# motherboard-board_cleanup.net
KiCad netlist of a schematic drawn in EAGLE
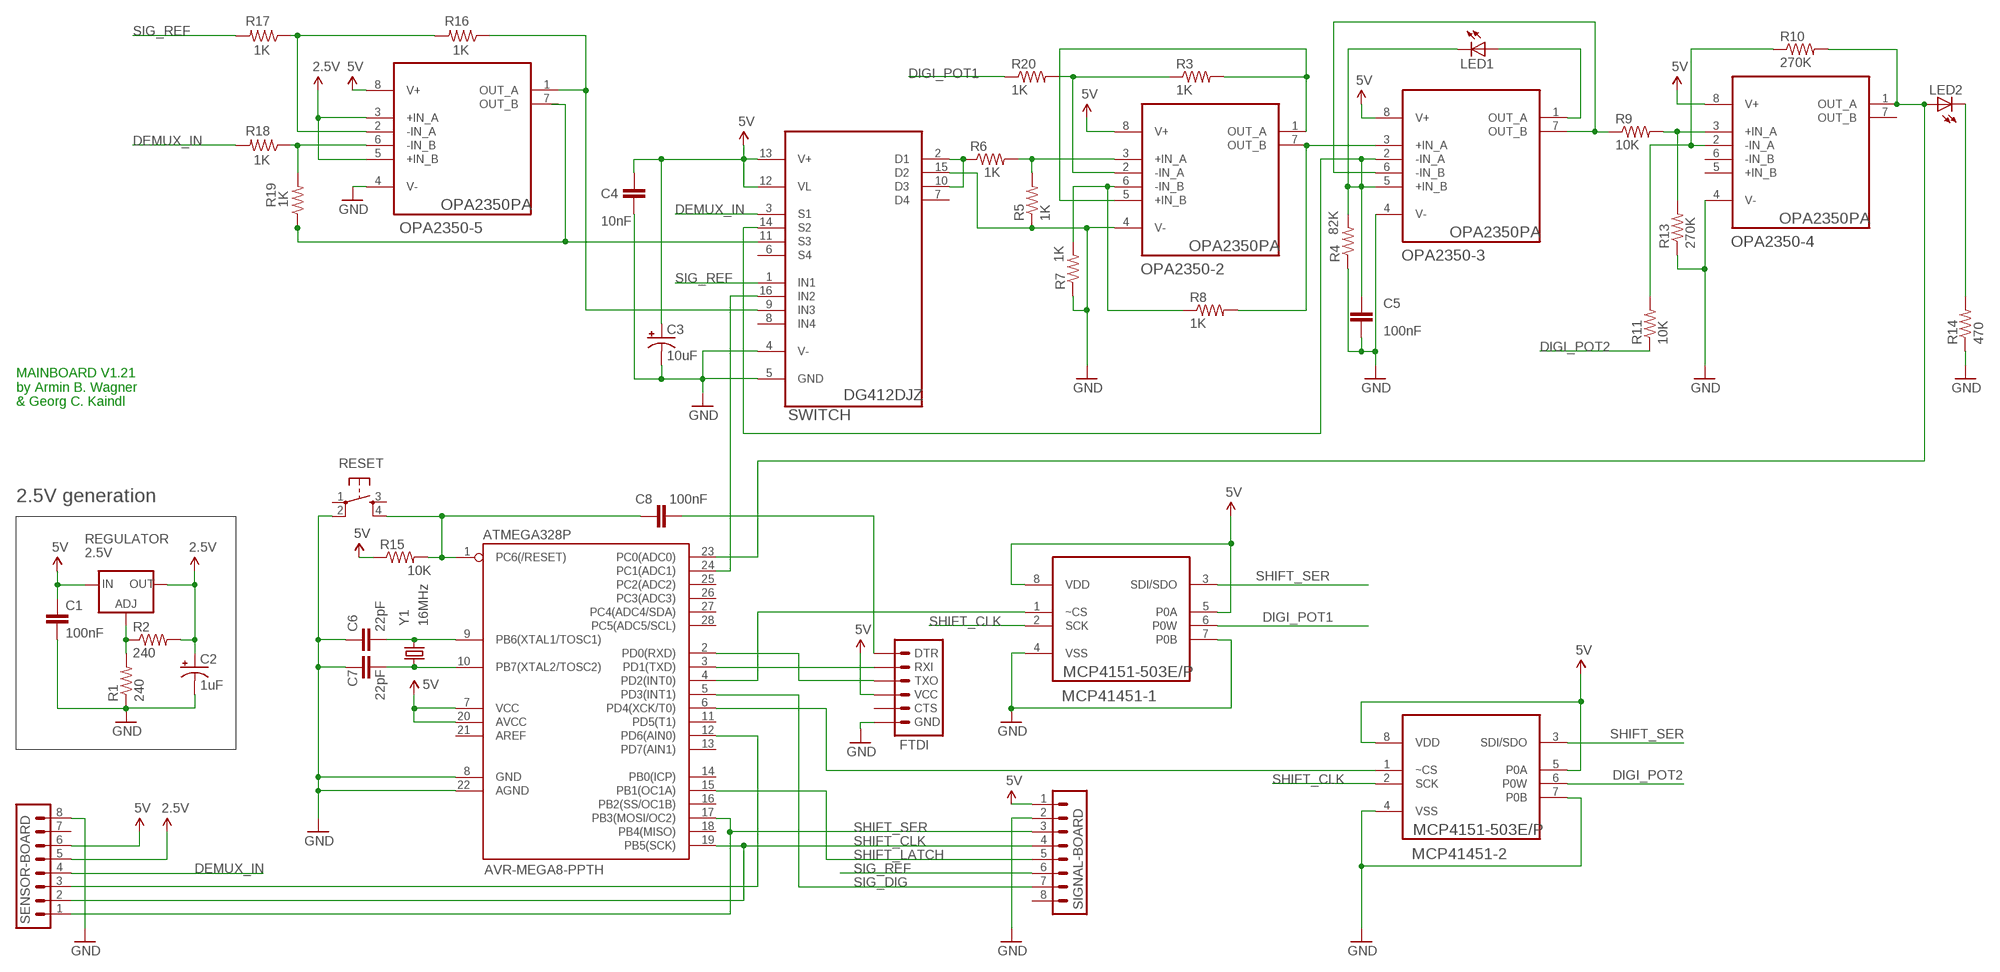
[diagram p0: schematic, sheet 1]

(export (version "E")
  (design (tool "Eeschema 10.0.6"))
  (components
    (comp (ref "ATMEGA328P")
      (value "AVR-MEGA8-PPTH")
      (footprint "eagle-import:DIL28-3")
      (libsource (lib "eagle-import") (part "AVR-MEGA8-PPTH"))
    )
    (comp (ref "C1")
      (value "100nF")
      (footprint "eagle-import:CAP-PTH-SMALL")
      (libsource (lib "eagle-import") (part "CAPPTH"))
    )
    (comp (ref "C2")
      (value "1uF")
      (footprint "eagle-import:CPOL-RADIAL-10UF-25V")
      (libsource (lib "eagle-import") (part "CAP_POLPTH2"))
    )
    (comp (ref "C3")
      (value "10uF")
      (footprint "eagle-import:CPOL-RADIAL-10UF-25V")
      (libsource (lib "eagle-import") (part "CAP_POLPTH2"))
    )
    (comp (ref "C4")
      (value "10nF")
      (footprint "eagle-import:CAP-PTH-SMALL")
      (libsource (lib "eagle-import") (part "CAPPTH"))
    )
    (comp (ref "C5")
      (value "100nF")
      (footprint "eagle-import:CAP-PTH-SMALL")
      (libsource (lib "eagle-import") (part "CAPPTH"))
    )
    (comp (ref "C6")
      (value "22pF")
      (footprint "eagle-import:CAP-PTH-SMALL2")
      (libsource (lib "eagle-import") (part "CAPPTH2"))
    )
    (comp (ref "C7")
      (value "22pF")
      (footprint "eagle-import:CAP-PTH-SMALL2")
      (libsource (lib "eagle-import") (part "CAPPTH2"))
    )
    (comp (ref "C8")
      (value "100nF")
      (footprint "eagle-import:CAP-PTH-SMALL2")
      (libsource (lib "eagle-import") (part "CAPPTH2"))
    )
    (comp (ref "FTDI")
      (value "ARDUINO_SERIAL_PROGRAMLONGPADS")
      (footprint "eagle-import:1X06_LONGPADS")
      (libsource (lib "eagle-import") (part "ARDUINO_SERIAL_PROGRAMLONGPADS"))
    )
    (comp (ref "LED1")
      (value "LED3MM")
      (footprint "eagle-import:LED3MM")
      (libsource (lib "eagle-import") (part "LED3MM"))
    )
    (comp (ref "LED2")
      (value "LED5MM")
      (footprint "eagle-import:LED5MM")
      (libsource (lib "eagle-import") (part "LED5MM"))
    )
    (comp (ref "MCP41451-1")
      (value "MCP4151-503E/P")
      (footprint "eagle-import:DIP254P762X533-8")
      (libsource (lib "eagle-import") (part "MCP4151-503E/P"))
    )
    (comp (ref "MCP41451-2")
      (value "MCP4151-503E/P")
      (footprint "eagle-import:DIP254P762X533-8")
      (libsource (lib "eagle-import") (part "MCP4151-503E/P"))
    )
    (comp (ref "OPA2350-2")
      (value "OPA2350PA")
      (footprint "eagle-import:DIP254P762X508-8")
      (libsource (lib "eagle-import") (part "OPA2350PA"))
    )
    (comp (ref "OPA2350-3")
      (value "OPA2350PA")
      (footprint "eagle-import:DIP254P762X508-8")
      (libsource (lib "eagle-import") (part "OPA2350PA"))
    )
    (comp (ref "OPA2350-4")
      (value "OPA2350PA")
      (footprint "eagle-import:DIP254P762X508-8")
      (libsource (lib "eagle-import") (part "OPA2350PA"))
    )
    (comp (ref "OPA2350-5")
      (value "OPA2350PA")
      (footprint "eagle-import:DIP254P762X508-8")
      (libsource (lib "eagle-import") (part "OPA2350PA"))
    )
    (comp (ref "R1")
      (value "240")
      (footprint "eagle-import:AXIAL-0.3")
      (libsource (lib "eagle-import") (part "RESISTORAXIAL-0.3"))
    )
    (comp (ref "R2")
      (value "240")
      (footprint "eagle-import:AXIAL-0.3")
      (libsource (lib "eagle-import") (part "RESISTORAXIAL-0.3"))
    )
    (comp (ref "R3")
      (value "1K")
      (footprint "eagle-import:AXIAL-0.3")
      (libsource (lib "eagle-import") (part "RESISTORAXIAL-0.3"))
    )
    (comp (ref "R4")
      (value "82K")
      (footprint "eagle-import:AXIAL-0.3")
      (libsource (lib "eagle-import") (part "RESISTORAXIAL-0.3"))
    )
    (comp (ref "R5")
      (value "1K")
      (footprint "eagle-import:AXIAL-0.3")
      (libsource (lib "eagle-import") (part "RESISTORAXIAL-0.3"))
    )
    (comp (ref "R6")
      (value "1K")
      (footprint "eagle-import:AXIAL-0.3")
      (libsource (lib "eagle-import") (part "RESISTORAXIAL-0.3"))
    )
    (comp (ref "R7")
      (value "1K")
      (footprint "eagle-import:AXIAL-0.3")
      (libsource (lib "eagle-import") (part "RESISTORAXIAL-0.3"))
    )
    (comp (ref "R8")
      (value "1K")
      (footprint "eagle-import:AXIAL-0.3")
      (libsource (lib "eagle-import") (part "RESISTORAXIAL-0.3"))
    )
    (comp (ref "R9")
      (value "10K")
      (footprint "eagle-import:AXIAL-0.3")
      (libsource (lib "eagle-import") (part "RESISTORAXIAL-0.3"))
    )
    (comp (ref "R10")
      (value "270K")
      (footprint "eagle-import:AXIAL-0.3")
      (libsource (lib "eagle-import") (part "RESISTORAXIAL-0.3"))
    )
    (comp (ref "R11")
      (value "10K")
      (footprint "eagle-import:AXIAL-0.3")
      (libsource (lib "eagle-import") (part "RESISTORAXIAL-0.3"))
    )
    (comp (ref "R13")
      (value "270K")
      (footprint "eagle-import:AXIAL-0.3")
      (libsource (lib "eagle-import") (part "RESISTORAXIAL-0.3"))
    )
    (comp (ref "R14")
      (value "470")
      (footprint "eagle-import:AXIAL-0.3")
      (libsource (lib "eagle-import") (part "RESISTORAXIAL-0.3"))
    )
    (comp (ref "R15")
      (value "10K")
      (footprint "eagle-import:AXIAL-0.3")
      (libsource (lib "eagle-import") (part "RESISTORAXIAL-0.3"))
    )
    (comp (ref "R16")
      (value "1K")
      (footprint "eagle-import:AXIAL-0.3")
      (libsource (lib "eagle-import") (part "RESISTORAXIAL-0.3"))
    )
    (comp (ref "R17")
      (value "1K")
      (footprint "eagle-import:AXIAL-0.3")
      (libsource (lib "eagle-import") (part "RESISTORAXIAL-0.3"))
    )
    (comp (ref "R18")
      (value "1K")
      (footprint "eagle-import:AXIAL-0.3")
      (libsource (lib "eagle-import") (part "RESISTORAXIAL-0.3"))
    )
    (comp (ref "R19")
      (value "1K")
      (footprint "eagle-import:AXIAL-0.3")
      (libsource (lib "eagle-import") (part "RESISTORAXIAL-0.3"))
    )
    (comp (ref "R20")
      (value "1K")
      (footprint "eagle-import:AXIAL-0.3")
      (libsource (lib "eagle-import") (part "RESISTORAXIAL-0.3"))
    )
    (comp (ref "REGULATOR")
      (value "2.5V")
      (footprint "eagle-import:TO220-ADJ")
      (libsource (lib "eagle-import") (part "V_REG_317SINK"))
    )
    (comp (ref "RESET")
      (value "TAC_SWITCHPTH")
      (footprint "eagle-import:TACTILE-PTH")
      (libsource (lib "eagle-import") (part "TAC_SWITCHPTH"))
    )
    (comp (ref "SENSOR-BOARD")
      (value "M08LONGPADS")
      (footprint "eagle-import:1X08_LONGPADS")
      (libsource (lib "eagle-import") (part "M08LONGPADS"))
    )
    (comp (ref "SIGNAL-BOARD")
      (value "M08LONGPADS")
      (footprint "eagle-import:1X08_LONGPADS")
      (libsource (lib "eagle-import") (part "M08LONGPADS"))
    )
    (comp (ref "SWITCH")
      (value "DG412DJZ")
      (footprint "eagle-import:DIP254P762X533-16")
      (libsource (lib "eagle-import") (part "DG412DJZ"))
    )
    (comp (ref "Y1")
      (value "16MHz")
      (footprint "eagle-import:HC49US")
      (libsource (lib "eagle-import") (part "CRYSTALHC49US"))
    )
  )
  (nets
    (net (code "1") (name "/DEMUX_IN") (class "Default")
      (node (ref "R18") (pin "P$2") (pinfunction "2_P$2") (pintype "passive"))
      (node (ref "SENSOR-BOARD") (pin "4") (pinfunction "4_4") (pintype "passive"))
      (node (ref "SWITCH") (pin "3") (pinfunction "S1_3") (pintype "input"))
    )
    (net (code "2") (name "/DIGI_POT1") (class "Default")
      (node (ref "MCP41451-1") (pin "6") (pinfunction "P0W_6") (pintype "passive"))
      (node (ref "R20") (pin "P$1") (pinfunction "1_P$1") (pintype "passive"))
    )
    (net (code "3") (name "/DIGI_POT2") (class "Default")
      (node (ref "MCP41451-2") (pin "6") (pinfunction "P0W_6") (pintype "passive"))
      (node (ref "R11") (pin "P$1") (pinfunction "1_P$1") (pintype "passive"))
    )
    (net (code "4") (name "/SHIFT_CLK") (class "Default")
      (node (ref "ATMEGA328P") (pin "19") (pinfunction "PB5(SCK)_19") (pintype "bidirectional"))
      (node (ref "MCP41451-1") (pin "2") (pinfunction "SCK_2") (pintype "input"))
      (node (ref "MCP41451-2") (pin "2") (pinfunction "SCK_2") (pintype "input"))
      (node (ref "SENSOR-BOARD") (pin "2") (pinfunction "2_2") (pintype "passive"))
      (node (ref "SIGNAL-BOARD") (pin "4") (pinfunction "4_4") (pintype "passive"))
    )
    (net (code "5") (name "/SHIFT_LATCH") (class "Default")
      (node (ref "ATMEGA328P") (pin "15") (pinfunction "PB1(OC1A)_15") (pintype "bidirectional"))
      (node (ref "SIGNAL-BOARD") (pin "5") (pinfunction "5_5") (pintype "passive"))
    )
    (net (code "6") (name "/SHIFT_SER") (class "Default")
      (node (ref "ATMEGA328P") (pin "17") (pinfunction "PB3(MOSI/OC2)_17") (pintype "bidirectional"))
      (node (ref "MCP41451-1") (pin "3") (pinfunction "SDI/SDO_3") (pintype "bidirectional"))
      (node (ref "MCP41451-2") (pin "3") (pinfunction "SDI/SDO_3") (pintype "bidirectional"))
      (node (ref "SENSOR-BOARD") (pin "1") (pinfunction "1_1") (pintype "passive"))
      (node (ref "SIGNAL-BOARD") (pin "3") (pinfunction "3_3") (pintype "passive"))
    )
    (net (code "7") (name "/SIG_DIG") (class "Default")
      (node (ref "ATMEGA328P") (pin "5") (pinfunction "PD3(INT1)_5") (pintype "bidirectional"))
      (node (ref "SIGNAL-BOARD") (pin "7") (pinfunction "7_7") (pintype "passive"))
    )
    (net (code "8") (name "/SIG_REF") (class "Default")
      (node (ref "R17") (pin "P$2") (pinfunction "2_P$2") (pintype "passive"))
      (node (ref "SIGNAL-BOARD") (pin "6") (pinfunction "6_6") (pintype "passive"))
      (node (ref "SWITCH") (pin "1") (pinfunction "IN1_1") (pintype "input"))
    )
    (net (code "9") (name "2.5V") (class "Default")
      (node (ref "C2") (pin "1") (pinfunction "+_1") (pintype "passive"))
      (node (ref "OPA2350-5") (pin "3") (pinfunction "+IN_A_3") (pintype "input"))
      (node (ref "OPA2350-5") (pin "5") (pinfunction "+IN_B_5") (pintype "input"))
      (node (ref "R2") (pin "P$2") (pinfunction "2_P$2") (pintype "passive"))
      (node (ref "REGULATOR") (pin "OUT") (pinfunction "OUT_OUT") (pintype "output"))
      (node (ref "SENSOR-BOARD") (pin "5") (pinfunction "5_5") (pintype "passive"))
    )
    (net (code "10") (name "5V") (class "Default")
      (node (ref "ATMEGA328P") (pin "20") (pinfunction "AVCC_20") (pintype "bidirectional"))
      (node (ref "ATMEGA328P") (pin "7") (pinfunction "VCC_7") (pintype "bidirectional"))
      (node (ref "C1") (pin "1") (pinfunction "1_1") (pintype "passive"))
      (node (ref "C3") (pin "1") (pinfunction "+_1") (pintype "passive"))
      (node (ref "C4") (pin "1") (pinfunction "1_1") (pintype "passive"))
      (node (ref "FTDI") (pin "4") (pinfunction "VCC_4") (pintype "passive"))
      (node (ref "MCP41451-1") (pin "5") (pinfunction "P0A_5") (pintype "passive"))
      (node (ref "MCP41451-1") (pin "8") (pinfunction "VDD_8") (pintype "power_in"))
      (node (ref "MCP41451-2") (pin "5") (pinfunction "P0A_5") (pintype "passive"))
      (node (ref "MCP41451-2") (pin "8") (pinfunction "VDD_8") (pintype "power_in"))
      (node (ref "OPA2350-2") (pin "8") (pinfunction "V+_8") (pintype "power_in"))
      (node (ref "OPA2350-3") (pin "8") (pinfunction "V+_8") (pintype "power_in"))
      (node (ref "OPA2350-4") (pin "8") (pinfunction "V+_8") (pintype "power_in"))
      (node (ref "OPA2350-5") (pin "8") (pinfunction "V+_8") (pintype "power_in"))
      (node (ref "R15") (pin "P$1") (pinfunction "1_P$1") (pintype "passive"))
      (node (ref "REGULATOR") (pin "IN") (pinfunction "IN_IN") (pintype "input"))
      (node (ref "SENSOR-BOARD") (pin "6") (pinfunction "6_6") (pintype "passive"))
      (node (ref "SIGNAL-BOARD") (pin "1") (pinfunction "1_1") (pintype "passive"))
      (node (ref "SWITCH") (pin "12") (pinfunction "VL_12") (pintype "power_in"))
      (node (ref "SWITCH") (pin "13") (pinfunction "V+_13") (pintype "power_in"))
    )
    (net (code "11") (name "GND") (class "Default")
      (node (ref "ATMEGA328P") (pin "22") (pinfunction "AGND_22") (pintype "bidirectional"))
      (node (ref "ATMEGA328P") (pin "8") (pinfunction "GND_8") (pintype "bidirectional"))
      (node (ref "C1") (pin "2") (pinfunction "2_2") (pintype "passive"))
      (node (ref "C2") (pin "2") (pinfunction "-_2") (pintype "passive"))
      (node (ref "C3") (pin "2") (pinfunction "-_2") (pintype "passive"))
      (node (ref "C4") (pin "2") (pinfunction "2_2") (pintype "passive"))
      (node (ref "C5") (pin "2") (pinfunction "2_2") (pintype "passive"))
      (node (ref "C6") (pin "1") (pinfunction "1_1") (pintype "passive"))
      (node (ref "C7") (pin "1") (pinfunction "1_1") (pintype "passive"))
      (node (ref "FTDI") (pin "6") (pinfunction "GND_6") (pintype "passive"))
      (node (ref "MCP41451-1") (pin "4") (pinfunction "VSS_4") (pintype "power_in"))
      (node (ref "MCP41451-1") (pin "7") (pinfunction "P0B_7") (pintype "passive"))
      (node (ref "MCP41451-2") (pin "4") (pinfunction "VSS_4") (pintype "power_in"))
      (node (ref "MCP41451-2") (pin "7") (pinfunction "P0B_7") (pintype "passive"))
      (node (ref "OPA2350-2") (pin "4") (pinfunction "V-_4") (pintype "power_in"))
      (node (ref "OPA2350-3") (pin "4") (pinfunction "V-_4") (pintype "power_in"))
      (node (ref "OPA2350-4") (pin "4") (pinfunction "V-_4") (pintype "power_in"))
      (node (ref "OPA2350-5") (pin "4") (pinfunction "V-_4") (pintype "power_in"))
      (node (ref "R1") (pin "P$1") (pinfunction "1_P$1") (pintype "passive"))
      (node (ref "R13") (pin "P$1") (pinfunction "1_P$1") (pintype "passive"))
      (node (ref "R14") (pin "P$1") (pinfunction "1_P$1") (pintype "passive"))
      (node (ref "R4") (pin "P$1") (pinfunction "1_P$1") (pintype "passive"))
      (node (ref "R5") (pin "P$1") (pinfunction "1_P$1") (pintype "passive"))
      (node (ref "R7") (pin "P$1") (pinfunction "1_P$1") (pintype "passive"))
      (node (ref "RESET") (pin "2") (pinfunction "2_2") (pintype "passive"))
      (node (ref "SENSOR-BOARD") (pin "8") (pinfunction "8_8") (pintype "passive"))
      (node (ref "SIGNAL-BOARD") (pin "2") (pinfunction "2_2") (pintype "passive"))
      (node (ref "SWITCH") (pin "15") (pinfunction "D2_15") (pintype "output"))
      (node (ref "SWITCH") (pin "4") (pinfunction "V-_4") (pintype "power_in"))
      (node (ref "SWITCH") (pin "5") (pinfunction "GND_5") (pintype "passive"))
    )
    (net (code "12") (name "Net-(ATMEGA328P-PB6(XTAL1{slash}TOSC1))") (class "Default")
      (node (ref "ATMEGA328P") (pin "9") (pinfunction "PB6(XTAL1/TOSC1)_9") (pintype "bidirectional"))
      (node (ref "C6") (pin "2") (pinfunction "2_2") (pintype "passive"))
      (node (ref "Y1") (pin "2") (pinfunction "2_2") (pintype "passive"))
    )
    (net (code "13") (name "Net-(ATMEGA328P-PB7(XTAL2{slash}TOSC2))") (class "Default")
      (node (ref "ATMEGA328P") (pin "10") (pinfunction "PB7(XTAL2/TOSC2)_10") (pintype "bidirectional"))
      (node (ref "C7") (pin "2") (pinfunction "2_2") (pintype "passive"))
      (node (ref "Y1") (pin "1") (pinfunction "1_1") (pintype "passive"))
    )
    (net (code "14") (name "Net-(ATMEGA328P-PC0(ADC0))") (class "Default")
      (node (ref "ATMEGA328P") (pin "23") (pinfunction "PC0(ADC0)_23") (pintype "bidirectional"))
      (node (ref "LED2") (pin "A") (pinfunction "A_A") (pintype "passive"))
      (node (ref "OPA2350-4") (pin "1") (pinfunction "OUT_A_1") (pintype "output"))
      (node (ref "R10") (pin "P$2") (pinfunction "2_P$2") (pintype "passive"))
    )
    (net (code "15") (name "Net-(ATMEGA328P-PC1(ADC1))") (class "Default")
      (node (ref "ATMEGA328P") (pin "24") (pinfunction "PC1(ADC1)_24") (pintype "bidirectional"))
      (node (ref "SWITCH") (pin "16") (pinfunction "IN2_16") (pintype "input"))
    )
    (net (code "16") (name "Net-(ATMEGA328P-PC6({slash}RESET))") (class "Default")
      (node (ref "ATMEGA328P") (pin "1") (pinfunction "PC6(/RESET)_1") (pintype "bidirectional"))
      (node (ref "C8") (pin "1") (pinfunction "1_1") (pintype "passive"))
      (node (ref "R15") (pin "P$2") (pinfunction "2_P$2") (pintype "passive"))
      (node (ref "RESET") (pin "4") (pinfunction "4_4") (pintype "passive"))
    )
    (net (code "17") (name "Net-(ATMEGA328P-PD0(RXD))") (class "Default")
      (node (ref "ATMEGA328P") (pin "2") (pinfunction "PD0(RXD)_2") (pintype "bidirectional"))
      (node (ref "FTDI") (pin "3") (pinfunction "TXO_3") (pintype "passive"))
    )
    (net (code "18") (name "Net-(ATMEGA328P-PD1(TXD))") (class "Default")
      (node (ref "ATMEGA328P") (pin "3") (pinfunction "PD1(TXD)_3") (pintype "bidirectional"))
      (node (ref "FTDI") (pin "2") (pinfunction "RXI_2") (pintype "passive"))
    )
    (net (code "19") (name "Net-(ATMEGA328P-PD2(INT0))") (class "Default")
      (node (ref "ATMEGA328P") (pin "4") (pinfunction "PD2(INT0)_4") (pintype "bidirectional"))
      (node (ref "MCP41451-1") (pin "1") (pinfunction "~{CS}_1") (pintype "input"))
    )
    (net (code "20") (name "Net-(ATMEGA328P-PD4(XCK{slash}T0))") (class "Default")
      (node (ref "ATMEGA328P") (pin "6") (pinfunction "PD4(XCK/T0)_6") (pintype "bidirectional"))
      (node (ref "MCP41451-2") (pin "1") (pinfunction "~{CS}_1") (pintype "input"))
    )
    (net (code "21") (name "Net-(ATMEGA328P-PD6(AIN0))") (class "Default")
      (node (ref "ATMEGA328P") (pin "12") (pinfunction "PD6(AIN0)_12") (pintype "bidirectional"))
      (node (ref "SENSOR-BOARD") (pin "3") (pinfunction "3_3") (pintype "passive"))
    )
    (net (code "22") (name "Net-(FTDI-DTR)") (class "Default")
      (node (ref "C8") (pin "2") (pinfunction "2_2") (pintype "passive"))
      (node (ref "FTDI") (pin "1") (pinfunction "DTR_1") (pintype "passive"))
    )
    (net (code "23") (name "Net-(LED1-C)") (class "Default")
      (node (ref "C5") (pin "1") (pinfunction "1_1") (pintype "passive"))
      (node (ref "LED1") (pin "K") (pinfunction "C_K") (pintype "passive"))
      (node (ref "OPA2350-3") (pin "2") (pinfunction "-IN_A_2") (pintype "input"))
      (node (ref "OPA2350-3") (pin "5") (pinfunction "+IN_B_5") (pintype "input"))
      (node (ref "R4") (pin "P$2") (pinfunction "2_P$2") (pintype "passive"))
      (node (ref "SWITCH") (pin "14") (pinfunction "S2_14") (pintype "input"))
    )
    (net (code "24") (name "Net-(LED2-C)") (class "Default")
      (node (ref "LED2") (pin "K") (pinfunction "C_K") (pintype "passive"))
      (node (ref "R14") (pin "P$2") (pinfunction "2_P$2") (pintype "passive"))
    )
    (net (code "25") (name "Net-(OPA2350-2-+IN_A)") (class "Default")
      (node (ref "OPA2350-2") (pin "3") (pinfunction "+IN_A_3") (pintype "input"))
      (node (ref "R5") (pin "P$2") (pinfunction "2_P$2") (pintype "passive"))
      (node (ref "R6") (pin "P$2") (pinfunction "2_P$2") (pintype "passive"))
    )
    (net (code "26") (name "Net-(OPA2350-2-+IN_B)") (class "Default")
      (node (ref "OPA2350-2") (pin "1") (pinfunction "OUT_A_1") (pintype "output"))
      (node (ref "OPA2350-2") (pin "5") (pinfunction "+IN_B_5") (pintype "input"))
      (node (ref "R3") (pin "P$2") (pinfunction "2_P$2") (pintype "passive"))
    )
    (net (code "27") (name "Net-(OPA2350-2--IN_A)") (class "Default")
      (node (ref "OPA2350-2") (pin "2") (pinfunction "-IN_A_2") (pintype "input"))
      (node (ref "R20") (pin "P$2") (pinfunction "2_P$2") (pintype "passive"))
      (node (ref "R3") (pin "P$1") (pinfunction "1_P$1") (pintype "passive"))
    )
    (net (code "28") (name "Net-(OPA2350-2--IN_B)") (class "Default")
      (node (ref "OPA2350-2") (pin "6") (pinfunction "-IN_B_6") (pintype "input"))
      (node (ref "R7") (pin "P$2") (pinfunction "2_P$2") (pintype "passive"))
      (node (ref "R8") (pin "P$1") (pinfunction "1_P$1") (pintype "passive"))
    )
    (net (code "29") (name "Net-(OPA2350-2-OUT_B)") (class "Default")
      (node (ref "OPA2350-2") (pin "7") (pinfunction "OUT_B_7") (pintype "output"))
      (node (ref "OPA2350-3") (pin "3") (pinfunction "+IN_A_3") (pintype "input"))
      (node (ref "R8") (pin "P$2") (pinfunction "2_P$2") (pintype "passive"))
    )
    (net (code "30") (name "Net-(OPA2350-3--IN_B)") (class "Default")
      (node (ref "OPA2350-3") (pin "6") (pinfunction "-IN_B_6") (pintype "input"))
      (node (ref "OPA2350-3") (pin "7") (pinfunction "OUT_B_7") (pintype "output"))
      (node (ref "R9") (pin "P$1") (pinfunction "1_P$1") (pintype "passive"))
    )
    (net (code "31") (name "Net-(OPA2350-3-OUT_A)") (class "Default")
      (node (ref "LED1") (pin "A") (pinfunction "A_A") (pintype "passive"))
      (node (ref "OPA2350-3") (pin "1") (pinfunction "OUT_A_1") (pintype "output"))
    )
    (net (code "32") (name "Net-(OPA2350-4-+IN_A)") (class "Default")
      (node (ref "OPA2350-4") (pin "3") (pinfunction "+IN_A_3") (pintype "input"))
      (node (ref "R13") (pin "P$2") (pinfunction "2_P$2") (pintype "passive"))
      (node (ref "R9") (pin "P$2") (pinfunction "2_P$2") (pintype "passive"))
    )
    (net (code "33") (name "Net-(OPA2350-4--IN_A)") (class "Default")
      (node (ref "OPA2350-4") (pin "2") (pinfunction "-IN_A_2") (pintype "input"))
      (node (ref "R10") (pin "P$1") (pinfunction "1_P$1") (pintype "passive"))
      (node (ref "R11") (pin "P$2") (pinfunction "2_P$2") (pintype "passive"))
    )
    (net (code "34") (name "Net-(OPA2350-5--IN_A)") (class "Default")
      (node (ref "OPA2350-5") (pin "2") (pinfunction "-IN_A_2") (pintype "input"))
      (node (ref "R16") (pin "P$2") (pinfunction "2_P$2") (pintype "passive"))
      (node (ref "R17") (pin "P$1") (pinfunction "1_P$1") (pintype "passive"))
    )
    (net (code "35") (name "Net-(OPA2350-5--IN_B)") (class "Default")
      (node (ref "OPA2350-5") (pin "6") (pinfunction "-IN_B_6") (pintype "input"))
      (node (ref "R18") (pin "P$1") (pinfunction "1_P$1") (pintype "passive"))
      (node (ref "R19") (pin "P$2") (pinfunction "2_P$2") (pintype "passive"))
    )
    (net (code "36") (name "Net-(OPA2350-5-OUT_A)") (class "Default")
      (node (ref "OPA2350-5") (pin "1") (pinfunction "OUT_A_1") (pintype "output"))
      (node (ref "R16") (pin "P$1") (pinfunction "1_P$1") (pintype "passive"))
      (node (ref "SWITCH") (pin "9") (pinfunction "IN3_9") (pintype "input"))
    )
    (net (code "37") (name "Net-(R1-2)") (class "Default")
      (node (ref "R1") (pin "P$2") (pinfunction "2_P$2") (pintype "passive"))
      (node (ref "R2") (pin "P$1") (pinfunction "1_P$1") (pintype "passive"))
      (node (ref "REGULATOR") (pin "ADJ") (pinfunction "ADJ_ADJ") (pintype "input"))
    )
    (net (code "38") (name "Net-(R6-1)") (class "Default")
      (node (ref "R6") (pin "P$1") (pinfunction "1_P$1") (pintype "passive"))
      (node (ref "SWITCH") (pin "10") (pinfunction "D3_10") (pintype "output"))
      (node (ref "SWITCH") (pin "2") (pinfunction "D1_2") (pintype "output"))
    )
    (net (code "39") (name "Net-(R19-1)") (class "Default")
      (node (ref "R19") (pin "P$1") (pinfunction "1_P$1") (pintype "passive"))
      (node (ref "SWITCH") (pin "11") (pinfunction "S3_11") (pintype "input"))
    )
    (net (code "40") (name "unconnected-(ATMEGA328P-AREF-Pad21)") (class "Default")
      (node (ref "ATMEGA328P") (pin "21") (pinfunction "AREF_21") (pintype "bidirectional"))
    )
    (net (code "41") (name "unconnected-(ATMEGA328P-PB0(ICP)-Pad14)") (class "Default")
      (node (ref "ATMEGA328P") (pin "14") (pinfunction "PB0(ICP)_14") (pintype "bidirectional"))
    )
    (net (code "42") (name "unconnected-(ATMEGA328P-PB2(SS{slash}OC1B)-Pad16)") (class "Default")
      (node (ref "ATMEGA328P") (pin "16") (pinfunction "PB2(SS/OC1B)_16") (pintype "bidirectional"))
    )
    (net (code "43") (name "unconnected-(ATMEGA328P-PB4(MISO)-Pad18)") (class "Default")
      (node (ref "ATMEGA328P") (pin "18") (pinfunction "PB4(MISO)_18") (pintype "bidirectional"))
    )
    (net (code "44") (name "unconnected-(ATMEGA328P-PC2(ADC2)-Pad25)") (class "Default")
      (node (ref "ATMEGA328P") (pin "25") (pinfunction "PC2(ADC2)_25") (pintype "bidirectional"))
    )
    (net (code "45") (name "unconnected-(ATMEGA328P-PC3(ADC3)-Pad26)") (class "Default")
      (node (ref "ATMEGA328P") (pin "26") (pinfunction "PC3(ADC3)_26") (pintype "bidirectional"))
    )
    (net (code "46") (name "unconnected-(ATMEGA328P-PC4(ADC4{slash}SDA)-Pad27)") (class "Default")
      (node (ref "ATMEGA328P") (pin "27") (pinfunction "PC4(ADC4/SDA)_27") (pintype "bidirectional"))
    )
    (net (code "47") (name "unconnected-(ATMEGA328P-PC5(ADC5{slash}SCL)-Pad28)") (class "Default")
      (node (ref "ATMEGA328P") (pin "28") (pinfunction "PC5(ADC5/SCL)_28") (pintype "bidirectional"))
    )
    (net (code "48") (name "unconnected-(ATMEGA328P-PD5(T1)-Pad11)") (class "Default")
      (node (ref "ATMEGA328P") (pin "11") (pinfunction "PD5(T1)_11") (pintype "bidirectional"))
    )
    (net (code "49") (name "unconnected-(ATMEGA328P-PD7(AIN1)-Pad13)") (class "Default")
      (node (ref "ATMEGA328P") (pin "13") (pinfunction "PD7(AIN1)_13") (pintype "bidirectional"))
    )
    (net (code "50") (name "unconnected-(FTDI-CTS-Pad5)") (class "Default")
      (node (ref "FTDI") (pin "5") (pinfunction "CTS_5") (pintype "passive"))
    )
    (net (code "51") (name "unconnected-(OPA2350-4-+IN_B-Pad5)") (class "Default")
      (node (ref "OPA2350-4") (pin "5") (pinfunction "+IN_B_5") (pintype "input"))
    )
    (net (code "52") (name "unconnected-(OPA2350-4--IN_B-Pad6)") (class "Default")
      (node (ref "OPA2350-4") (pin "6") (pinfunction "-IN_B_6") (pintype "input"))
    )
    (net (code "53") (name "unconnected-(OPA2350-4-OUT_B-Pad7)") (class "Default")
      (node (ref "OPA2350-4") (pin "7") (pinfunction "OUT_B_7") (pintype "output"))
    )
    (net (code "54") (name "unconnected-(OPA2350-5-OUT_B-Pad7)") (class "Default")
      (node (ref "OPA2350-5") (pin "7") (pinfunction "OUT_B_7") (pintype "output"))
    )
    (net (code "55") (name "unconnected-(RESET-Pad1)") (class "Default")
      (node (ref "RESET") (pin "1") (pinfunction "1_1") (pintype "passive"))
    )
    (net (code "56") (name "unconnected-(RESET-Pad3)") (class "Default")
      (node (ref "RESET") (pin "3") (pinfunction "3_3") (pintype "passive"))
    )
    (net (code "57") (name "unconnected-(SENSOR-BOARD-Pad7)") (class "Default")
      (node (ref "SENSOR-BOARD") (pin "7") (pinfunction "7_7") (pintype "passive"))
    )
    (net (code "58") (name "unconnected-(SIGNAL-BOARD-Pad8)") (class "Default")
      (node (ref "SIGNAL-BOARD") (pin "8") (pinfunction "8_8") (pintype "passive"))
    )
    (net (code "59") (name "unconnected-(SWITCH-D4-Pad7)") (class "Default")
      (node (ref "SWITCH") (pin "7") (pinfunction "D4_7") (pintype "output"))
    )
    (net (code "60") (name "unconnected-(SWITCH-IN4-Pad8)") (class "Default")
      (node (ref "SWITCH") (pin "8") (pinfunction "IN4_8") (pintype "input"))
    )
    (net (code "61") (name "unconnected-(SWITCH-S4-Pad6)") (class "Default")
      (node (ref "SWITCH") (pin "6") (pinfunction "S4_6") (pintype "input"))
    )
  )
)
